# SoC_RGMII.net
KiCad netlist of a schematic drawn in Altium Designer
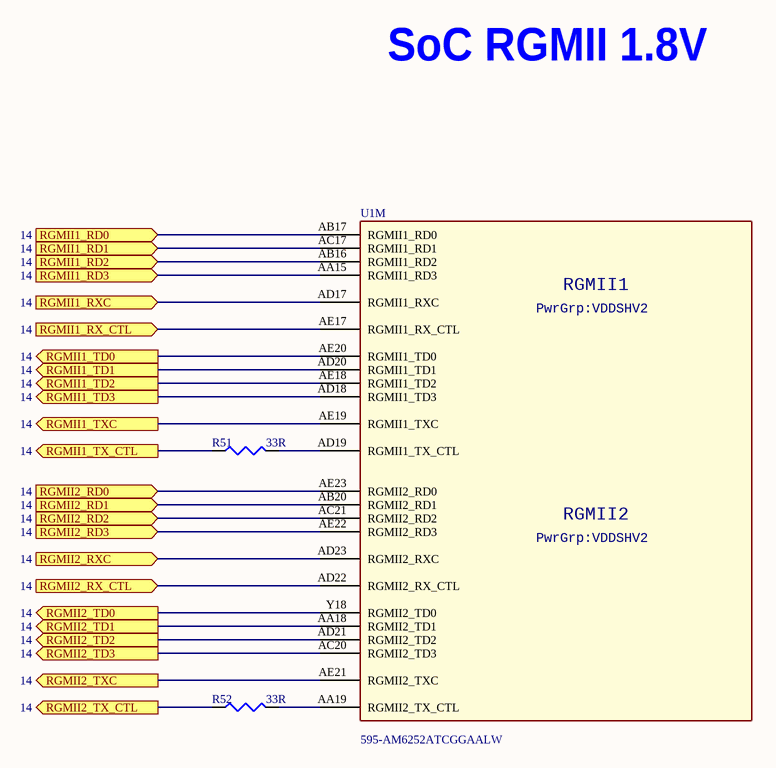
[diagram p0: SoC RGMII.SchDoc]

(export (version "E")
  (design (tool "Eeschema 10.0.6"))
  (components
    (comp (ref "R51")
      (value "33R")
      (footprint "R0201")
      (description "RES 33 OHM 1% 1/20W 0201")
      (fields
        (field (name "MANUFACTURER") "Yageo")
        (field (name "MANUFACTURER PART NUMBER") "RC0201FR-0733RL")
      )
      (libsource (lib "Schlib AM625") (part "RC0201FR-0733RL"))
    )
    (comp (ref "R52")
      (value "33R")
      (footprint "R0201")
      (description "RES 33 OHM 1% 1/20W 0201")
      (fields
        (field (name "MANUFACTURER") "Yageo")
        (field (name "MANUFACTURER PART NUMBER") "RC0201FR-0733RL")
      )
      (libsource (lib "Schlib AM625") (part "RC0201FR-0733RL"))
    )
    (comp (ref "U1")
      (value "AM62-EVM_BGA425")
      (footprint "BGA425C50P25X25_1300X1300X89")
      (description "ARM® Cortex®-A53 Microprocessor IC Sitara™ 2 Core, 64-Bit 1.4GHz 425-FCCSP (13x13)")
      (fields
        (field (name "MANUFACTURER") "Texas Instruments")
        (field (name "MANUFACTURER PART NUMBER") "AM6252ATCGGAALW")
        (field (name "SUPPLIER PART NUMBER 1") "595-AM6252ATCGGAALW")
      )
      (libsource (lib "Schlib AM625") (part "AM62-EVM_BGA425"))
    )
  )
  (nets
    (net (code "1") (name "/RGMII1_RD0") (class "Default")
      (node (ref "U1") (pin "AB17") (pinfunction "RGMII1_RD0_AB17") (pintype "passive"))
    )
    (net (code "2") (name "/RGMII1_RD1") (class "Default")
      (node (ref "U1") (pin "AC17") (pinfunction "RGMII1_RD1_AC17") (pintype "passive"))
    )
    (net (code "3") (name "/RGMII1_RD2") (class "Default")
      (node (ref "U1") (pin "AB16") (pinfunction "RGMII1_RD2_AB16") (pintype "passive"))
    )
    (net (code "4") (name "/RGMII1_RD3") (class "Default")
      (node (ref "U1") (pin "AA15") (pinfunction "RGMII1_RD3_AA15") (pintype "passive"))
    )
    (net (code "5") (name "/RGMII1_RXC") (class "Default")
      (node (ref "U1") (pin "AD17") (pinfunction "RGMII1_RXC_AD17") (pintype "passive"))
    )
    (net (code "6") (name "/RGMII1_RX_CTL") (class "Default")
      (node (ref "U1") (pin "AE17") (pinfunction "RGMII1_RX_CTL_AE17") (pintype "passive"))
    )
    (net (code "7") (name "/RGMII1_TD0") (class "Default")
      (node (ref "U1") (pin "AE20") (pinfunction "RGMII1_TD0_AE20") (pintype "passive"))
    )
    (net (code "8") (name "/RGMII1_TD1") (class "Default")
      (node (ref "U1") (pin "AD20") (pinfunction "RGMII1_TD1_AD20") (pintype "passive"))
    )
    (net (code "9") (name "/RGMII1_TD2") (class "Default")
      (node (ref "U1") (pin "AE18") (pinfunction "RGMII1_TD2_AE18") (pintype "passive"))
    )
    (net (code "10") (name "/RGMII1_TD3") (class "Default")
      (node (ref "U1") (pin "AD18") (pinfunction "RGMII1_TD3_AD18") (pintype "passive"))
    )
    (net (code "11") (name "/RGMII1_TXC") (class "Default")
      (node (ref "U1") (pin "AE19") (pinfunction "RGMII1_TXC_AE19") (pintype "passive"))
    )
    (net (code "12") (name "/RGMII1_TX_CTL") (class "Default")
      (node (ref "R51") (pin "1") (pinfunction "1_1") (pintype "passive"))
    )
    (net (code "13") (name "/RGMII2_RD0") (class "Default")
      (node (ref "U1") (pin "AE23") (pinfunction "RGMII2_RD0_AE23") (pintype "passive"))
    )
    (net (code "14") (name "/RGMII2_RD1") (class "Default")
      (node (ref "U1") (pin "AB20") (pinfunction "RGMII2_RD1_AB20") (pintype "passive"))
    )
    (net (code "15") (name "/RGMII2_RD2") (class "Default")
      (node (ref "U1") (pin "AC21") (pinfunction "RGMII2_RD2_AC21") (pintype "passive"))
    )
    (net (code "16") (name "/RGMII2_RD3") (class "Default")
      (node (ref "U1") (pin "AE22") (pinfunction "RGMII2_RD3_AE22") (pintype "passive"))
    )
    (net (code "17") (name "/RGMII2_RXC") (class "Default")
      (node (ref "U1") (pin "AD23") (pinfunction "RGMII2_RXC_AD23") (pintype "passive"))
    )
    (net (code "18") (name "/RGMII2_RX_CTL") (class "Default")
      (node (ref "U1") (pin "AD22") (pinfunction "RGMII2_RX_CTL_AD22") (pintype "passive"))
    )
    (net (code "19") (name "/RGMII2_TD0") (class "Default")
      (node (ref "U1") (pin "Y18") (pinfunction "RGMII2_TD0_Y18") (pintype "passive"))
    )
    (net (code "20") (name "/RGMII2_TD1") (class "Default")
      (node (ref "U1") (pin "AA18") (pinfunction "RGMII2_TD1_AA18") (pintype "passive"))
    )
    (net (code "21") (name "/RGMII2_TD2") (class "Default")
      (node (ref "U1") (pin "AD21") (pinfunction "RGMII2_TD2_AD21") (pintype "passive"))
    )
    (net (code "22") (name "/RGMII2_TD3") (class "Default")
      (node (ref "U1") (pin "AC20") (pinfunction "RGMII2_TD3_AC20") (pintype "passive"))
    )
    (net (code "23") (name "/RGMII2_TXC") (class "Default")
      (node (ref "U1") (pin "AE21") (pinfunction "RGMII2_TXC_AE21") (pintype "passive"))
    )
    (net (code "24") (name "/RGMII2_TX_CTL") (class "Default")
      (node (ref "R52") (pin "1") (pinfunction "1_1") (pintype "passive"))
    )
    (net (code "25") (name "Net-(U1M-RGMII1_TX_CTL)") (class "Default")
      (node (ref "R51") (pin "2") (pinfunction "2_2") (pintype "passive"))
      (node (ref "U1") (pin "AD19") (pinfunction "RGMII1_TX_CTL_AD19") (pintype "passive"))
    )
    (net (code "26") (name "Net-(U1M-RGMII2_TX_CTL)") (class "Default")
      (node (ref "R52") (pin "2") (pinfunction "2_2") (pintype "passive"))
      (node (ref "U1") (pin "AA19") (pinfunction "RGMII2_TX_CTL_AA19") (pintype "passive"))
    )
  )
)
